# Bodenplatine_v001.net
KiCad netlist of a schematic drawn in EAGLE
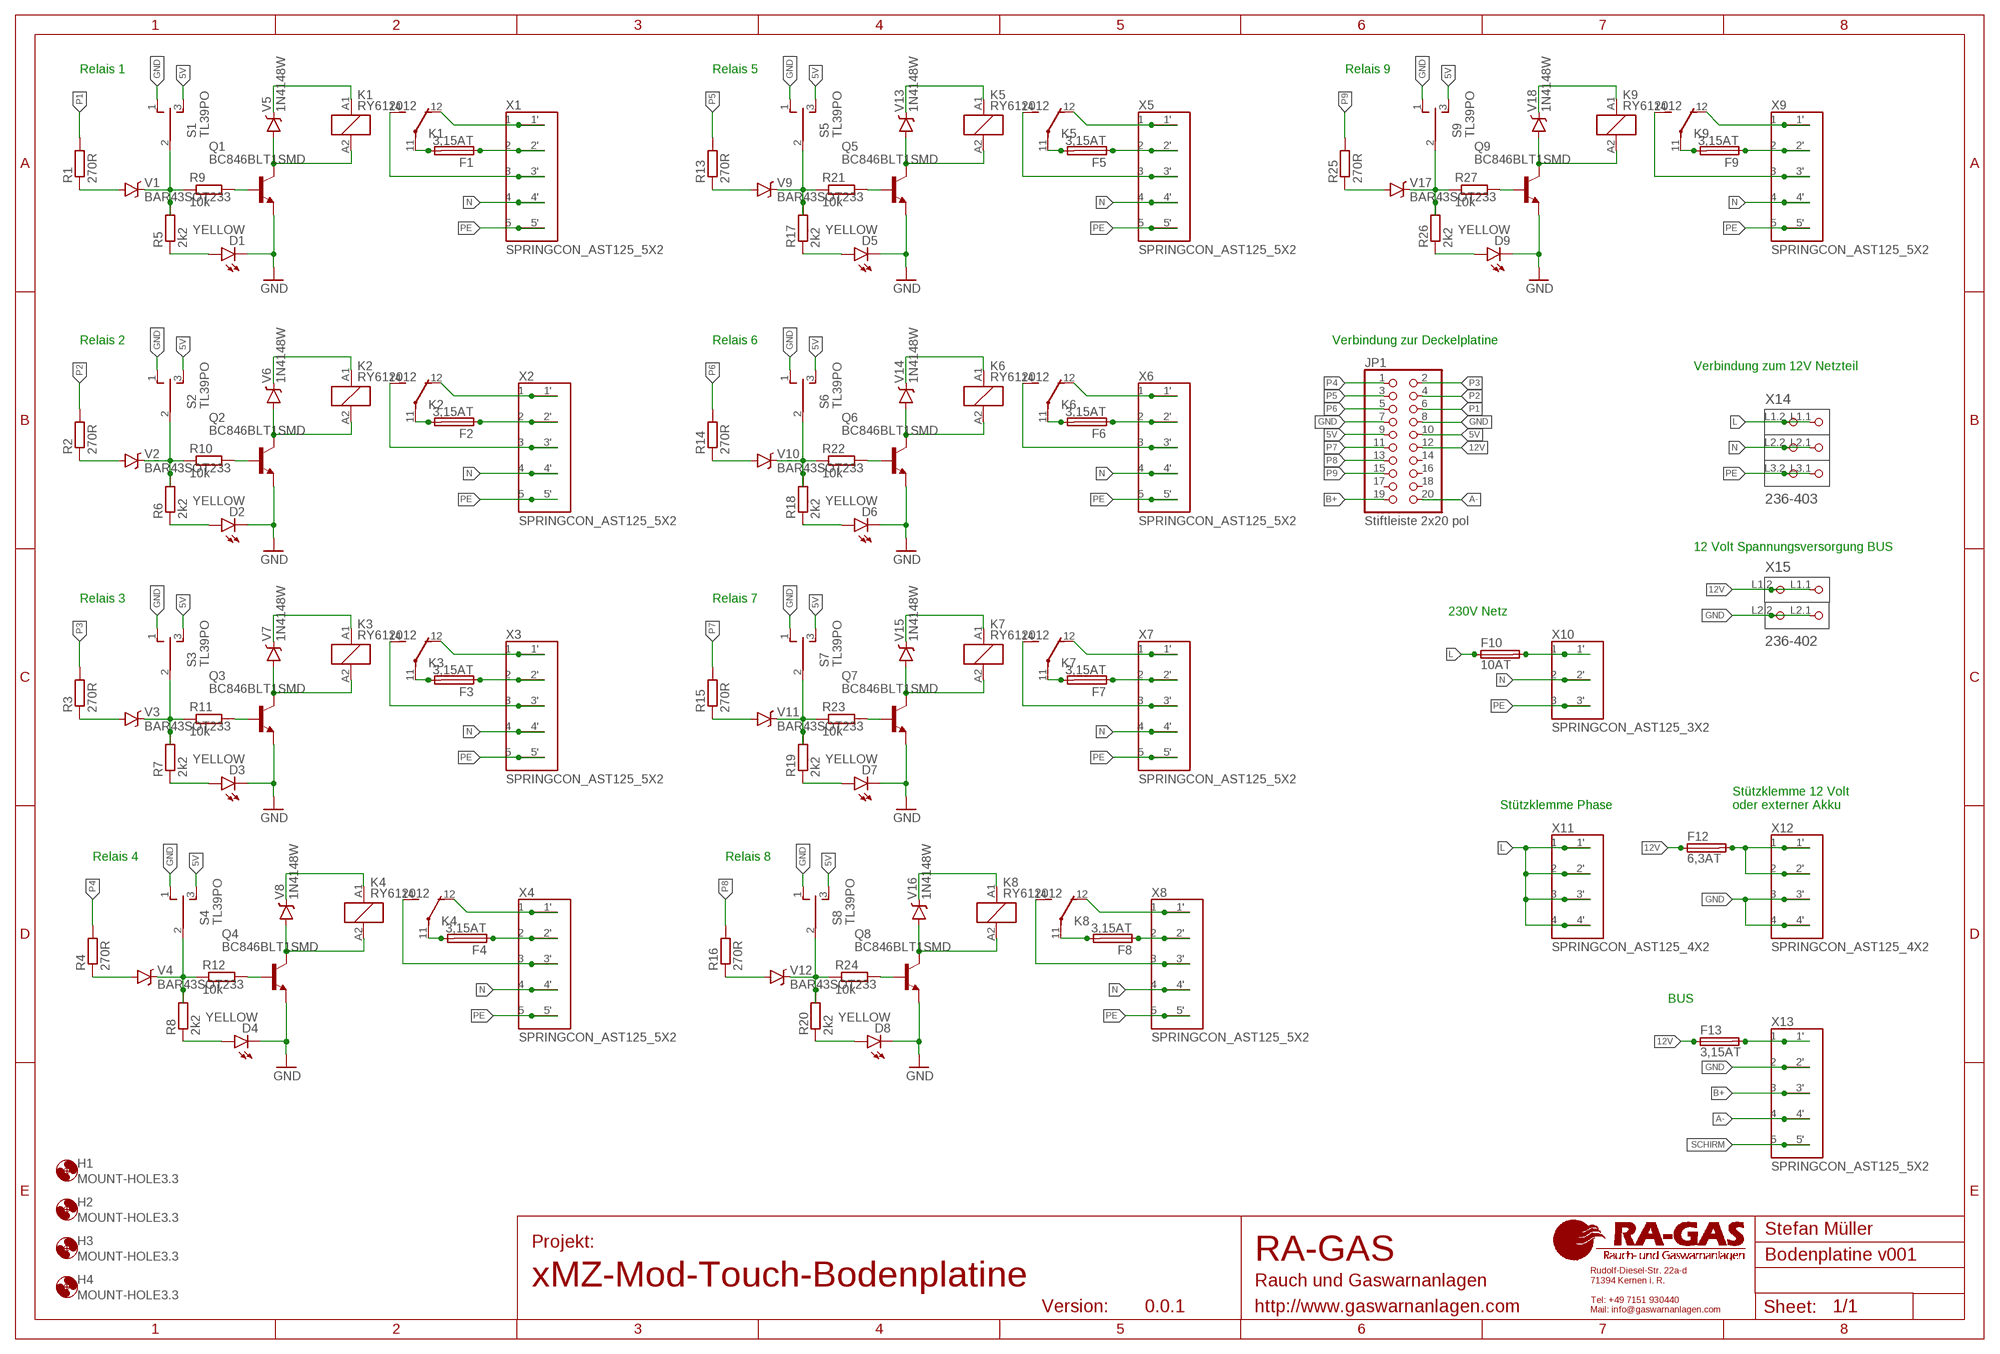
[diagram p0: schematic, sheet 1]

(export (version "E")
  (design (tool "Eeschema 10.0.6"))
  (components
    (comp (ref "D1")
      (value "YELLOW")
      (footprint "eagle-import:LED-1206")
      (fields (field (name "MF") "KINGBRIGHT") (field (name "MPN") "KP-3216SYC"))
      (libsource (lib "eagle-import") (part "LED-YELLOWLARGE"))
    )
    (comp (ref "D2")
      (value "YELLOW")
      (footprint "eagle-import:LED-1206")
      (fields (field (name "MF") "KINGBRIGHT") (field (name "MPN") "KP-3216SYC"))
      (libsource (lib "eagle-import") (part "LED-YELLOWLARGE"))
    )
    (comp (ref "D3")
      (value "YELLOW")
      (footprint "eagle-import:LED-1206")
      (fields (field (name "MF") "KINGBRIGHT") (field (name "MPN") "KP-3216SYC"))
      (libsource (lib "eagle-import") (part "LED-YELLOWLARGE"))
    )
    (comp (ref "D4")
      (value "YELLOW")
      (footprint "eagle-import:LED-1206")
      (fields (field (name "MF") "KINGBRIGHT") (field (name "MPN") "KP-3216SYC"))
      (libsource (lib "eagle-import") (part "LED-YELLOWLARGE"))
    )
    (comp (ref "D5")
      (value "YELLOW")
      (footprint "eagle-import:LED-1206")
      (fields (field (name "MF") "KINGBRIGHT") (field (name "MPN") "KP-3216SYC"))
      (libsource (lib "eagle-import") (part "LED-YELLOWLARGE"))
    )
    (comp (ref "D6")
      (value "YELLOW")
      (footprint "eagle-import:LED-1206")
      (fields (field (name "MF") "KINGBRIGHT") (field (name "MPN") "KP-3216SYC"))
      (libsource (lib "eagle-import") (part "LED-YELLOWLARGE"))
    )
    (comp (ref "D7")
      (value "YELLOW")
      (footprint "eagle-import:LED-1206")
      (fields (field (name "MF") "KINGBRIGHT") (field (name "MPN") "KP-3216SYC"))
      (libsource (lib "eagle-import") (part "LED-YELLOWLARGE"))
    )
    (comp (ref "D8")
      (value "YELLOW")
      (footprint "eagle-import:LED-1206")
      (fields (field (name "MF") "KINGBRIGHT") (field (name "MPN") "KP-3216SYC"))
      (libsource (lib "eagle-import") (part "LED-YELLOWLARGE"))
    )
    (comp (ref "D9")
      (value "YELLOW")
      (footprint "eagle-import:LED-1206")
      (fields (field (name "MF") "KINGBRIGHT") (field (name "MPN") "KP-3216SYC"))
      (libsource (lib "eagle-import") (part "LED-YELLOWLARGE"))
    )
    (comp (ref "F1")
      (value "3,15AT")
      (footprint "eagle-import:FPG4")
      (libsource (lib "eagle-import") (part "FPG4"))
    )
    (comp (ref "F2")
      (value "3,15AT")
      (footprint "eagle-import:FPG4")
      (libsource (lib "eagle-import") (part "FPG4"))
    )
    (comp (ref "F3")
      (value "3,15AT")
      (footprint "eagle-import:FPG4")
      (libsource (lib "eagle-import") (part "FPG4"))
    )
    (comp (ref "F4")
      (value "3,15AT")
      (footprint "eagle-import:FPG4")
      (libsource (lib "eagle-import") (part "FPG4"))
    )
    (comp (ref "F5")
      (value "3,15AT")
      (footprint "eagle-import:FPG4")
      (libsource (lib "eagle-import") (part "FPG4"))
    )
    (comp (ref "F6")
      (value "3,15AT")
      (footprint "eagle-import:FPG4")
      (libsource (lib "eagle-import") (part "FPG4"))
    )
    (comp (ref "F7")
      (value "3,15AT")
      (footprint "eagle-import:FPG4")
      (libsource (lib "eagle-import") (part "FPG4"))
    )
    (comp (ref "F8")
      (value "3,15AT")
      (footprint "eagle-import:FPG4")
      (libsource (lib "eagle-import") (part "FPG4"))
    )
    (comp (ref "F9")
      (value "3,15AT")
      (footprint "eagle-import:FPG4")
      (libsource (lib "eagle-import") (part "FPG4"))
    )
    (comp (ref "F10")
      (value "10AT")
      (footprint "eagle-import:FPG4")
      (libsource (lib "eagle-import") (part "FPG4"))
    )
    (comp (ref "F12")
      (value "6,3AT")
      (footprint "eagle-import:FPG4")
      (libsource (lib "eagle-import") (part "FPG4"))
    )
    (comp (ref "F13")
      (value "3,15AT")
      (footprint "eagle-import:FPG4")
      (libsource (lib "eagle-import") (part "FPG4"))
    )
    (comp (ref "H1")
      (value "MOUNT-HOLE3.3")
      (footprint "eagle-import:3,3")
      (libsource (lib "eagle-import") (part "MOUNT-HOLE3.3"))
    )
    (comp (ref "H2")
      (value "MOUNT-HOLE3.3")
      (footprint "eagle-import:3,3")
      (libsource (lib "eagle-import") (part "MOUNT-HOLE3.3"))
    )
    (comp (ref "H3")
      (value "MOUNT-HOLE3.3")
      (footprint "eagle-import:3,3")
      (libsource (lib "eagle-import") (part "MOUNT-HOLE3.3"))
    )
    (comp (ref "H4")
      (value "MOUNT-HOLE3.3")
      (footprint "eagle-import:3,3")
      (libsource (lib "eagle-import") (part "MOUNT-HOLE3.3"))
    )
    (comp (ref "JP1")
      (value "Stiftleiste 2x20 pol")
      (footprint "eagle-import:2X10")
      (fields (field (name "MF") "TE CONNECTIVITY / AMP") (field (name "MPN") "825440-5"))
      (libsource (lib "eagle-import") (part "PINHD-2X10"))
    )
    (comp (ref "K1")
      (value "RY612012")
      (footprint "eagle-import:RY-II")
      (fields
        (field (name "MF") "TYCO ELECTRONICS")
        (field (name "MF_1") "TE CONNECTIVITY / SCHRACK")
        (field (name "MPN") "V23061B1005A301")
        (field (name "OC_FARNELL") "1023958")
      )
      (libsource (lib "eagle-import") (part "RY?162012"))
    )
    (comp (ref "K2")
      (value "RY612012")
      (footprint "eagle-import:RY-II")
      (fields
        (field (name "MF") "TYCO ELECTRONICS")
        (field (name "MF_1") "TE CONNECTIVITY / SCHRACK")
        (field (name "MPN") "V23061B1005A301")
        (field (name "OC_FARNELL") "1023958")
      )
      (libsource (lib "eagle-import") (part "RY?162012"))
    )
    (comp (ref "K3")
      (value "RY612012")
      (footprint "eagle-import:RY-II")
      (fields
        (field (name "MF") "TYCO ELECTRONICS")
        (field (name "MF_1") "TE CONNECTIVITY / SCHRACK")
        (field (name "MPN") "V23061B1005A301")
        (field (name "OC_FARNELL") "1023958")
      )
      (libsource (lib "eagle-import") (part "RY?162012"))
    )
    (comp (ref "K4")
      (value "RY612012")
      (footprint "eagle-import:RY-II")
      (fields
        (field (name "MF") "TYCO ELECTRONICS")
        (field (name "MF_1") "TE CONNECTIVITY / SCHRACK")
        (field (name "MPN") "V23061B1005A301")
        (field (name "OC_FARNELL") "1023958")
      )
      (libsource (lib "eagle-import") (part "RY?162012"))
    )
    (comp (ref "K5")
      (value "RY612012")
      (footprint "eagle-import:RY-II")
      (fields
        (field (name "MF") "TYCO ELECTRONICS")
        (field (name "MF_1") "TE CONNECTIVITY / SCHRACK")
        (field (name "MPN") "V23061B1005A301")
        (field (name "OC_FARNELL") "1023958")
      )
      (libsource (lib "eagle-import") (part "RY?162012"))
    )
    (comp (ref "K6")
      (value "RY612012")
      (footprint "eagle-import:RY-II")
      (fields
        (field (name "MF") "TYCO ELECTRONICS")
        (field (name "MF_1") "TE CONNECTIVITY / SCHRACK")
        (field (name "MPN") "V23061B1005A301")
        (field (name "OC_FARNELL") "1023958")
      )
      (libsource (lib "eagle-import") (part "RY?162012"))
    )
    (comp (ref "K7")
      (value "RY612012")
      (footprint "eagle-import:RY-II")
      (fields
        (field (name "MF") "TYCO ELECTRONICS")
        (field (name "MF_1") "TE CONNECTIVITY / SCHRACK")
        (field (name "MPN") "V23061B1005A301")
        (field (name "OC_FARNELL") "1023958")
      )
      (libsource (lib "eagle-import") (part "RY?162012"))
    )
    (comp (ref "K8")
      (value "RY612012")
      (footprint "eagle-import:RY-II")
      (fields
        (field (name "MF") "TYCO ELECTRONICS")
        (field (name "MF_1") "TE CONNECTIVITY / SCHRACK")
        (field (name "MPN") "V23061B1005A301")
        (field (name "OC_FARNELL") "1023958")
      )
      (libsource (lib "eagle-import") (part "RY?162012"))
    )
    (comp (ref "K9")
      (value "RY612012")
      (footprint "eagle-import:RY-II")
      (fields
        (field (name "MF") "TYCO ELECTRONICS")
        (field (name "MF_1") "TE CONNECTIVITY / SCHRACK")
        (field (name "MPN") "V23061B1005A301")
        (field (name "OC_FARNELL") "1023958")
      )
      (libsource (lib "eagle-import") (part "RY?162012"))
    )
    (comp (ref "Q1")
      (value "BC846BLT1SMD")
      (footprint "eagle-import:SOT23")
      (fields (field (name "MF") "ON SEMICONDUCTOR") (field (name "MPN") "BC846BWT1G"))
      (libsource (lib "eagle-import") (part "BC846SMDBLT1"))
    )
    (comp (ref "Q2")
      (value "BC846BLT1SMD")
      (footprint "eagle-import:SOT23")
      (fields (field (name "MF") "ON SEMICONDUCTOR") (field (name "MPN") "BC846BWT1G"))
      (libsource (lib "eagle-import") (part "BC846SMDBLT1"))
    )
    (comp (ref "Q3")
      (value "BC846BLT1SMD")
      (footprint "eagle-import:SOT23")
      (fields (field (name "MF") "ON SEMICONDUCTOR") (field (name "MPN") "BC846BWT1G"))
      (libsource (lib "eagle-import") (part "BC846SMDBLT1"))
    )
    (comp (ref "Q4")
      (value "BC846BLT1SMD")
      (footprint "eagle-import:SOT23")
      (fields (field (name "MF") "ON SEMICONDUCTOR") (field (name "MPN") "BC846BWT1G"))
      (libsource (lib "eagle-import") (part "BC846SMDBLT1"))
    )
    (comp (ref "Q5")
      (value "BC846BLT1SMD")
      (footprint "eagle-import:SOT23")
      (fields (field (name "MF") "ON SEMICONDUCTOR") (field (name "MPN") "BC846BWT1G"))
      (libsource (lib "eagle-import") (part "BC846SMDBLT1"))
    )
    (comp (ref "Q6")
      (value "BC846BLT1SMD")
      (footprint "eagle-import:SOT23")
      (fields (field (name "MF") "ON SEMICONDUCTOR") (field (name "MPN") "BC846BWT1G"))
      (libsource (lib "eagle-import") (part "BC846SMDBLT1"))
    )
    (comp (ref "Q7")
      (value "BC846BLT1SMD")
      (footprint "eagle-import:SOT23")
      (fields (field (name "MF") "ON SEMICONDUCTOR") (field (name "MPN") "BC846BWT1G"))
      (libsource (lib "eagle-import") (part "BC846SMDBLT1"))
    )
    (comp (ref "Q8")
      (value "BC846BLT1SMD")
      (footprint "eagle-import:SOT23")
      (fields (field (name "MF") "ON SEMICONDUCTOR") (field (name "MPN") "BC846BWT1G"))
      (libsource (lib "eagle-import") (part "BC846SMDBLT1"))
    )
    (comp (ref "Q9")
      (value "BC846BLT1SMD")
      (footprint "eagle-import:SOT23")
      (fields (field (name "MF") "ON SEMICONDUCTOR") (field (name "MPN") "BC846BWT1G"))
      (libsource (lib "eagle-import") (part "BC846SMDBLT1"))
    )
    (comp (ref "R1")
      (value "270R")
      (footprint "eagle-import:M0805")
      (fields (field (name "MF") "MULTICOMP") (field (name "MPN") "MC01W08055270R"))
      (libsource (lib "eagle-import") (part "R-EU_M0805"))
    )
    (comp (ref "R2")
      (value "270R")
      (footprint "eagle-import:M0805")
      (fields (field (name "MF") "MULTICOMP") (field (name "MPN") "MC01W08055270R"))
      (libsource (lib "eagle-import") (part "R-EU_M0805"))
    )
    (comp (ref "R3")
      (value "270R")
      (footprint "eagle-import:M0805")
      (fields (field (name "MF") "MULTICOMP") (field (name "MPN") "MC01W08055270R"))
      (libsource (lib "eagle-import") (part "R-EU_M0805"))
    )
    (comp (ref "R4")
      (value "270R")
      (footprint "eagle-import:M0805")
      (fields (field (name "MF") "MULTICOMP") (field (name "MPN") "MC01W08055270R"))
      (libsource (lib "eagle-import") (part "R-EU_M0805"))
    )
    (comp (ref "R5")
      (value "2k2")
      (footprint "eagle-import:R0603")
      (fields (field (name "MF") "MULTICOMP") (field (name "MPN") "MC0063W060352K2"))
      (libsource (lib "eagle-import") (part "R-EU_R0603"))
    )
    (comp (ref "R6")
      (value "2k2")
      (footprint "eagle-import:R0603")
      (fields (field (name "MF") "MULTICOMP") (field (name "MPN") "MC0063W060352K2"))
      (libsource (lib "eagle-import") (part "R-EU_R0603"))
    )
    (comp (ref "R7")
      (value "2k2")
      (footprint "eagle-import:R0603")
      (fields (field (name "MF") "MULTICOMP") (field (name "MPN") "MC0063W060352K2"))
      (libsource (lib "eagle-import") (part "R-EU_R0603"))
    )
    (comp (ref "R8")
      (value "2k2")
      (footprint "eagle-import:R0603")
      (fields (field (name "MF") "MULTICOMP") (field (name "MPN") "MC0063W060352K2"))
      (libsource (lib "eagle-import") (part "R-EU_R0603"))
    )
    (comp (ref "R9")
      (value "10k")
      (footprint "eagle-import:R0603")
      (fields (field (name "MF") "TE CONNECTIVITY / NEOHM") (field (name "MPN") "CPF0603B10KE1"))
      (libsource (lib "eagle-import") (part "R-EU_R0603"))
    )
    (comp (ref "R10")
      (value "10k")
      (footprint "eagle-import:R0603")
      (fields (field (name "MF") "TE CONNECTIVITY / NEOHM") (field (name "MPN") "CPF0603B10KE1"))
      (libsource (lib "eagle-import") (part "R-EU_R0603"))
    )
    (comp (ref "R11")
      (value "10k")
      (footprint "eagle-import:R0603")
      (fields (field (name "MF") "TE CONNECTIVITY / NEOHM") (field (name "MPN") "CPF0603B10KE1"))
      (libsource (lib "eagle-import") (part "R-EU_R0603"))
    )
    (comp (ref "R12")
      (value "10k")
      (footprint "eagle-import:R0603")
      (fields (field (name "MF") "TE CONNECTIVITY / NEOHM") (field (name "MPN") "CPF0603B10KE1"))
      (libsource (lib "eagle-import") (part "R-EU_R0603"))
    )
    (comp (ref "R13")
      (value "270R")
      (footprint "eagle-import:M0805")
      (fields (field (name "MF") "MULTICOMP") (field (name "MPN") "MC01W08055270R"))
      (libsource (lib "eagle-import") (part "R-EU_M0805"))
    )
    (comp (ref "R14")
      (value "270R")
      (footprint "eagle-import:M0805")
      (fields (field (name "MF") "MULTICOMP") (field (name "MPN") "MC01W08055270R"))
      (libsource (lib "eagle-import") (part "R-EU_M0805"))
    )
    (comp (ref "R15")
      (value "270R")
      (footprint "eagle-import:M0805")
      (fields (field (name "MF") "MULTICOMP") (field (name "MPN") "MC01W08055270R"))
      (libsource (lib "eagle-import") (part "R-EU_M0805"))
    )
    (comp (ref "R16")
      (value "270R")
      (footprint "eagle-import:M0805")
      (fields (field (name "MF") "MULTICOMP") (field (name "MPN") "MC01W08055270R"))
      (libsource (lib "eagle-import") (part "R-EU_M0805"))
    )
    (comp (ref "R17")
      (value "2k2")
      (footprint "eagle-import:R0603")
      (fields (field (name "MF") "MULTICOMP") (field (name "MPN") "MC0063W060352K2"))
      (libsource (lib "eagle-import") (part "R-EU_R0603"))
    )
    (comp (ref "R18")
      (value "2k2")
      (footprint "eagle-import:R0603")
      (fields (field (name "MF") "MULTICOMP") (field (name "MPN") "MC0063W060352K2"))
      (libsource (lib "eagle-import") (part "R-EU_R0603"))
    )
    (comp (ref "R19")
      (value "2k2")
      (footprint "eagle-import:R0603")
      (fields (field (name "MF") "MULTICOMP") (field (name "MPN") "MC0063W060352K2"))
      (libsource (lib "eagle-import") (part "R-EU_R0603"))
    )
    (comp (ref "R20")
      (value "2k2")
      (footprint "eagle-import:R0603")
      (fields (field (name "MF") "MULTICOMP") (field (name "MPN") "MC0063W060352K2"))
      (libsource (lib "eagle-import") (part "R-EU_R0603"))
    )
    (comp (ref "R21")
      (value "10k")
      (footprint "eagle-import:R0603")
      (fields (field (name "MF") "TE CONNECTIVITY / NEOHM") (field (name "MPN") "CPF0603B10KE1"))
      (libsource (lib "eagle-import") (part "R-EU_R0603"))
    )
    (comp (ref "R22")
      (value "10k")
      (footprint "eagle-import:R0603")
      (fields (field (name "MF") "TE CONNECTIVITY / NEOHM") (field (name "MPN") "CPF0603B10KE1"))
      (libsource (lib "eagle-import") (part "R-EU_R0603"))
    )
    (comp (ref "R23")
      (value "10k")
      (footprint "eagle-import:R0603")
      (fields (field (name "MF") "TE CONNECTIVITY / NEOHM") (field (name "MPN") "CPF0603B10KE1"))
      (libsource (lib "eagle-import") (part "R-EU_R0603"))
    )
    (comp (ref "R24")
      (value "10k")
      (footprint "eagle-import:R0603")
      (fields (field (name "MF") "TE CONNECTIVITY / NEOHM") (field (name "MPN") "CPF0603B10KE1"))
      (libsource (lib "eagle-import") (part "R-EU_R0603"))
    )
    (comp (ref "R25")
      (value "270R")
      (footprint "eagle-import:M0805")
      (fields (field (name "MF") "MULTICOMP") (field (name "MPN") "MC01W08055270R"))
      (libsource (lib "eagle-import") (part "R-EU_M0805"))
    )
    (comp (ref "R26")
      (value "2k2")
      (footprint "eagle-import:R0603")
      (fields (field (name "MF") "MULTICOMP") (field (name "MPN") "MC0063W060352K2"))
      (libsource (lib "eagle-import") (part "R-EU_R0603"))
    )
    (comp (ref "R27")
      (value "10k")
      (footprint "eagle-import:R0603")
      (fields (field (name "MF") "TE CONNECTIVITY / NEOHM") (field (name "MPN") "CPF0603B10KE1"))
      (libsource (lib "eagle-import") (part "R-EU_R0603"))
    )
    (comp (ref "S1")
      (value "TL39PO")
      (footprint "eagle-import:TL3XPO")
      (fields (field (name "MF") "TE CONNECTIVITY / ALCOSWITCH") (field (name "MPN") "A103SYCQ04"))
      (libsource (lib "eagle-import") (part "TL39PO"))
    )
    (comp (ref "S2")
      (value "TL39PO")
      (footprint "eagle-import:TL3XPO")
      (fields (field (name "MF") "TE CONNECTIVITY / ALCOSWITCH") (field (name "MPN") "A103SYCQ04"))
      (libsource (lib "eagle-import") (part "TL39PO"))
    )
    (comp (ref "S3")
      (value "TL39PO")
      (footprint "eagle-import:TL3XPO")
      (fields (field (name "MF") "TE CONNECTIVITY / ALCOSWITCH") (field (name "MPN") "A103SYCQ04"))
      (libsource (lib "eagle-import") (part "TL39PO"))
    )
    (comp (ref "S4")
      (value "TL39PO")
      (footprint "eagle-import:TL3XPO")
      (fields (field (name "MF") "TE CONNECTIVITY / ALCOSWITCH") (field (name "MPN") "A103SYCQ04"))
      (libsource (lib "eagle-import") (part "TL39PO"))
    )
    (comp (ref "S5")
      (value "TL39PO")
      (footprint "eagle-import:TL3XPO")
      (fields (field (name "MF") "TE CONNECTIVITY / ALCOSWITCH") (field (name "MPN") "A103SYCQ04"))
      (libsource (lib "eagle-import") (part "TL39PO"))
    )
    (comp (ref "S6")
      (value "TL39PO")
      (footprint "eagle-import:TL3XPO")
      (fields (field (name "MF") "TE CONNECTIVITY / ALCOSWITCH") (field (name "MPN") "A103SYCQ04"))
      (libsource (lib "eagle-import") (part "TL39PO"))
    )
    (comp (ref "S7")
      (value "TL39PO")
      (footprint "eagle-import:TL3XPO")
      (fields (field (name "MF") "TE CONNECTIVITY / ALCOSWITCH") (field (name "MPN") "A103SYCQ04"))
      (libsource (lib "eagle-import") (part "TL39PO"))
    )
    (comp (ref "S8")
      (value "TL39PO")
      (footprint "eagle-import:TL3XPO")
      (fields (field (name "MF") "TE CONNECTIVITY / ALCOSWITCH") (field (name "MPN") "A103SYCQ04"))
      (libsource (lib "eagle-import") (part "TL39PO"))
    )
    (comp (ref "S9")
      (value "TL39PO")
      (footprint "eagle-import:TL3XPO")
      (fields (field (name "MF") "TE CONNECTIVITY / ALCOSWITCH") (field (name "MPN") "A103SYCQ04"))
      (libsource (lib "eagle-import") (part "TL39PO"))
    )
    (comp (ref "V1")
      (value "BAR43SOT233")
      (footprint "eagle-import:SOT23")
      (fields (field (name "MF") "FAIRCHILD SEMICONDUCTOR") (field (name "MPN") "BAR43"))
      (libsource (lib "eagle-import") (part "BAR43SOT233"))
    )
    (comp (ref "V2")
      (value "BAR43SOT233")
      (footprint "eagle-import:SOT23")
      (fields (field (name "MF") "FAIRCHILD SEMICONDUCTOR") (field (name "MPN") "BAR43"))
      (libsource (lib "eagle-import") (part "BAR43SOT233"))
    )
    (comp (ref "V3")
      (value "BAR43SOT233")
      (footprint "eagle-import:SOT23")
      (fields (field (name "MF") "FAIRCHILD SEMICONDUCTOR") (field (name "MPN") "BAR43"))
      (libsource (lib "eagle-import") (part "BAR43SOT233"))
    )
    (comp (ref "V4")
      (value "BAR43SOT233")
      (footprint "eagle-import:SOT23")
      (fields (field (name "MF") "FAIRCHILD SEMICONDUCTOR") (field (name "MPN") "BAR43"))
      (libsource (lib "eagle-import") (part "BAR43SOT233"))
    )
    (comp (ref "V5")
      (value "1N4148W")
      (footprint "eagle-import:MINIMELF")
      (fields (field (name "MF") "VISHAY") (field (name "MPN") "LL4148-GS08"))
      (libsource (lib "eagle-import") (part "LL4148"))
    )
    (comp (ref "V6")
      (value "1N4148W")
      (footprint "eagle-import:MINIMELF")
      (fields (field (name "MF") "VISHAY") (field (name "MPN") "LL4148-GS08"))
      (libsource (lib "eagle-import") (part "LL4148"))
    )
    (comp (ref "V7")
      (value "1N4148W")
      (footprint "eagle-import:MINIMELF")
      (fields (field (name "MF") "VISHAY") (field (name "MPN") "LL4148-GS08"))
      (libsource (lib "eagle-import") (part "LL4148"))
    )
    (comp (ref "V8")
      (value "1N4148W")
      (footprint "eagle-import:MINIMELF")
      (fields (field (name "MF") "VISHAY") (field (name "MPN") "LL4148-GS08"))
      (libsource (lib "eagle-import") (part "LL4148"))
    )
    (comp (ref "V9")
      (value "BAR43SOT233")
      (footprint "eagle-import:SOT23")
      (fields (field (name "MF") "FAIRCHILD SEMICONDUCTOR") (field (name "MPN") "BAR43"))
      (libsource (lib "eagle-import") (part "BAR43SOT233"))
    )
    (comp (ref "V10")
      (value "BAR43SOT233")
      (footprint "eagle-import:SOT23")
      (fields (field (name "MF") "FAIRCHILD SEMICONDUCTOR") (field (name "MPN") "BAR43"))
      (libsource (lib "eagle-import") (part "BAR43SOT233"))
    )
    (comp (ref "V11")
      (value "BAR43SOT233")
      (footprint "eagle-import:SOT23")
      (fields (field (name "MF") "FAIRCHILD SEMICONDUCTOR") (field (name "MPN") "BAR43"))
      (libsource (lib "eagle-import") (part "BAR43SOT233"))
    )
    (comp (ref "V12")
      (value "BAR43SOT233")
      (footprint "eagle-import:SOT23")
      (fields (field (name "MF") "FAIRCHILD SEMICONDUCTOR") (field (name "MPN") "BAR43"))
      (libsource (lib "eagle-import") (part "BAR43SOT233"))
    )
    (comp (ref "V13")
      (value "1N4148W")
      (footprint "eagle-import:MINIMELF")
      (fields (field (name "MF") "VISHAY") (field (name "MPN") "LL4148-GS08"))
      (libsource (lib "eagle-import") (part "LL4148"))
    )
    (comp (ref "V14")
      (value "1N4148W")
      (footprint "eagle-import:MINIMELF")
      (fields (field (name "MF") "VISHAY") (field (name "MPN") "LL4148-GS08"))
      (libsource (lib "eagle-import") (part "LL4148"))
    )
    (comp (ref "V15")
      (value "1N4148W")
      (footprint "eagle-import:MINIMELF")
      (fields (field (name "MF") "VISHAY") (field (name "MPN") "LL4148-GS08"))
      (libsource (lib "eagle-import") (part "LL4148"))
    )
    (comp (ref "V16")
      (value "1N4148W")
      (footprint "eagle-import:MINIMELF")
      (fields (field (name "MF") "VISHAY") (field (name "MPN") "LL4148-GS08"))
      (libsource (lib "eagle-import") (part "LL4148"))
    )
    (comp (ref "V17")
      (value "BAR43SOT233")
      (footprint "eagle-import:SOT23")
      (fields (field (name "MF") "FAIRCHILD SEMICONDUCTOR") (field (name "MPN") "BAR43"))
      (libsource (lib "eagle-import") (part "BAR43SOT233"))
    )
    (comp (ref "V18")
      (value "1N4148W")
      (footprint "eagle-import:MINIMELF")
      (fields (field (name "MF") "VISHAY") (field (name "MPN") "LL4148-GS08"))
      (libsource (lib "eagle-import") (part "LL4148"))
    )
    (comp (ref "X1")
      (value "SPRINGCON_AST125_5X2")
      (footprint "eagle-import:SPRINGCON_AST125_5X2")
      (libsource (lib "eagle-import") (part "SPRINGCON_AST125_5X2"))
    )
    (comp (ref "X2")
      (value "SPRINGCON_AST125_5X2")
      (footprint "eagle-import:SPRINGCON_AST125_5X2")
      (libsource (lib "eagle-import") (part "SPRINGCON_AST125_5X2"))
    )
    (comp (ref "X3")
      (value "SPRINGCON_AST125_5X2")
      (footprint "eagle-import:SPRINGCON_AST125_5X2")
      (libsource (lib "eagle-import") (part "SPRINGCON_AST125_5X2"))
    )
    (comp (ref "X4")
      (value "SPRINGCON_AST125_5X2")
      (footprint "eagle-import:SPRINGCON_AST125_5X2")
      (libsource (lib "eagle-import") (part "SPRINGCON_AST125_5X2"))
    )
    (comp (ref "X5")
      (value "SPRINGCON_AST125_5X2")
      (footprint "eagle-import:SPRINGCON_AST125_5X2")
      (libsource (lib "eagle-import") (part "SPRINGCON_AST125_5X2"))
    )
    (comp (ref "X6")
      (value "SPRINGCON_AST125_5X2")
      (footprint "eagle-import:SPRINGCON_AST125_5X2")
      (libsource (lib "eagle-import") (part "SPRINGCON_AST125_5X2"))
    )
    (comp (ref "X7")
      (value "SPRINGCON_AST125_5X2")
      (footprint "eagle-import:SPRINGCON_AST125_5X2")
      (libsource (lib "eagle-import") (part "SPRINGCON_AST125_5X2"))
    )
    (comp (ref "X8")
      (value "SPRINGCON_AST125_5X2")
      (footprint "eagle-import:SPRINGCON_AST125_5X2")
      (libsource (lib "eagle-import") (part "SPRINGCON_AST125_5X2"))
    )
    (comp (ref "X9")
      (value "SPRINGCON_AST125_5X2")
      (footprint "eagle-import:SPRINGCON_AST125_5X2")
      (libsource (lib "eagle-import") (part "SPRINGCON_AST125_5X2"))
    )
    (comp (ref "X10")
      (value "SPRINGCON_AST125_3X2")
      (footprint "eagle-import:SPRINGCON_AST125_3X2")
      (libsource (lib "eagle-import") (part "SPRINGCON_AST125_3X2"))
    )
    (comp (ref "X11")
      (value "SPRINGCON_AST125_4X2")
      (footprint "eagle-import:SPRINGCON_AST125_4X2")
      (libsource (lib "eagle-import") (part "SPRINGCON_AST125_4X2"))
    )
    (comp (ref "X12")
      (value "SPRINGCON_AST125_4X2")
      (footprint "eagle-import:SPRINGCON_AST125_4X2")
      (libsource (lib "eagle-import") (part "SPRINGCON_AST125_4X2"))
    )
    (comp (ref "X13")
      (value "SPRINGCON_AST125_5X2")
      (footprint "eagle-import:SPRINGCON_AST125_5X2")
      (libsource (lib "eagle-import") (part "SPRINGCON_AST125_5X2"))
    )
    (comp (ref "X14")
      (value "236-403")
      (footprint "eagle-import:P-236-403")
      (fields (field (name "MF") "WAGO"))
      (libsource (lib "eagle-import") (part "236-403"))
    )
    (comp (ref "X15")
      (value "236-402")
      (footprint "eagle-import:P-236-402")
      (fields (field (name "MF") "WAGO"))
      (libsource (lib "eagle-import") (part "236-402"))
    )
  )
  (nets
    (net (code "1") (name "5V") (class "Default")
      (node (ref "JP1") (pin "10") (pinfunction "10_10") (pintype "passive"))
      (node (ref "JP1") (pin "9") (pinfunction "9_9") (pintype "passive"))
      (node (ref "S1") (pin "3") (pinfunction "S_3") (pintype "passive"))
      (node (ref "S2") (pin "3") (pinfunction "S_3") (pintype "passive"))
      (node (ref "S3") (pin "3") (pinfunction "S_3") (pintype "passive"))
      (node (ref "S4") (pin "3") (pinfunction "S_3") (pintype "passive"))
      (node (ref "S5") (pin "3") (pinfunction "S_3") (pintype "passive"))
      (node (ref "S6") (pin "3") (pinfunction "S_3") (pintype "passive"))
      (node (ref "S7") (pin "3") (pinfunction "S_3") (pintype "passive"))
      (node (ref "S8") (pin "3") (pinfunction "S_3") (pintype "passive"))
      (node (ref "S9") (pin "3") (pinfunction "S_3") (pintype "passive"))
    )
    (net (code "2") (name "12V") (class "Default")
      (node (ref "F12") (pin "1") (pinfunction "1_1") (pintype "passive"))
      (node (ref "F12") (pin "1'") (pinfunction "1_1'") (pintype "passive"))
      (node (ref "F13") (pin "1") (pinfunction "1_1") (pintype "passive"))
      (node (ref "F13") (pin "1'") (pinfunction "1_1'") (pintype "passive"))
      (node (ref "JP1") (pin "12") (pinfunction "12_12") (pintype "passive"))
      (node (ref "X15") (pin "L1.1") (pinfunction "P1.1_L1.1") (pintype "bidirectional"))
      (node (ref "X15") (pin "L1.2") (pinfunction "P1.2_L1.2") (pintype "bidirectional"))
    )
    (net (code "3") (name "A-") (class "Default")
      (node (ref "JP1") (pin "20") (pinfunction "20_20") (pintype "passive"))
      (node (ref "X13") (pin "4") (pinfunction "4_4") (pintype "passive"))
      (node (ref "X13") (pin "4'") (pinfunction "4_4'") (pintype "passive"))
    )
    (net (code "4") (name "B+") (class "Default")
      (node (ref "JP1") (pin "19") (pinfunction "19_19") (pintype "passive"))
      (node (ref "X13") (pin "3") (pinfunction "3_3") (pintype "passive"))
      (node (ref "X13") (pin "3'") (pinfunction "3_3'") (pintype "passive"))
    )
    (net (code "5") (name "GND") (class "Default")
      (node (ref "D1") (pin "C") (pinfunction "C_C") (pintype "passive"))
      (node (ref "D2") (pin "C") (pinfunction "C_C") (pintype "passive"))
      (node (ref "D3") (pin "C") (pinfunction "C_C") (pintype "passive"))
      (node (ref "D4") (pin "C") (pinfunction "C_C") (pintype "passive"))
      (node (ref "D5") (pin "C") (pinfunction "C_C") (pintype "passive"))
      (node (ref "D6") (pin "C") (pinfunction "C_C") (pintype "passive"))
      (node (ref "D7") (pin "C") (pinfunction "C_C") (pintype "passive"))
      (node (ref "D8") (pin "C") (pinfunction "C_C") (pintype "passive"))
      (node (ref "D9") (pin "C") (pinfunction "C_C") (pintype "passive"))
      (node (ref "JP1") (pin "7") (pinfunction "7_7") (pintype "passive"))
      (node (ref "JP1") (pin "8") (pinfunction "8_8") (pintype "passive"))
      (node (ref "Q1") (pin "2") (pinfunction "E_2") (pintype "passive"))
      (node (ref "Q2") (pin "2") (pinfunction "E_2") (pintype "passive"))
      (node (ref "Q3") (pin "2") (pinfunction "E_2") (pintype "passive"))
      (node (ref "Q4") (pin "2") (pinfunction "E_2") (pintype "passive"))
      (node (ref "Q5") (pin "2") (pinfunction "E_2") (pintype "passive"))
      (node (ref "Q6") (pin "2") (pinfunction "E_2") (pintype "passive"))
      (node (ref "Q7") (pin "2") (pinfunction "E_2") (pintype "passive"))
      (node (ref "Q8") (pin "2") (pinfunction "E_2") (pintype "passive"))
      (node (ref "Q9") (pin "2") (pinfunction "E_2") (pintype "passive"))
      (node (ref "S1") (pin "1") (pinfunction "O_1") (pintype "passive"))
      (node (ref "S2") (pin "1") (pinfunction "O_1") (pintype "passive"))
      (node (ref "S3") (pin "1") (pinfunction "O_1") (pintype "passive"))
      (node (ref "S4") (pin "1") (pinfunction "O_1") (pintype "passive"))
      (node (ref "S5") (pin "1") (pinfunction "O_1") (pintype "passive"))
      (node (ref "S6") (pin "1") (pinfunction "O_1") (pintype "passive"))
      (node (ref "S7") (pin "1") (pinfunction "O_1") (pintype "passive"))
      (node (ref "S8") (pin "1") (pinfunction "O_1") (pintype "passive"))
      (node (ref "S9") (pin "1") (pinfunction "O_1") (pintype "passive"))
      (node (ref "X12") (pin "3") (pinfunction "3_3") (pintype "passive"))
      (node (ref "X12") (pin "3'") (pinfunction "3_3'") (pintype "passive"))
      (node (ref "X12") (pin "4") (pinfunction "4_4") (pintype "passive"))
      (node (ref "X12") (pin "4'") (pinfunction "4_4'") (pintype "passive"))
      (node (ref "X13") (pin "2") (pinfunction "2_2") (pintype "passive"))
      (node (ref "X13") (pin "2'") (pinfunction "2_2'") (pintype "passive"))
      (node (ref "X15") (pin "L2.1") (pinfunction "P2.1_L2.1") (pintype "bidirectional"))
      (node (ref "X15") (pin "L2.2") (pinfunction "P2.2_L2.2") (pintype "bidirectional"))
    )
    (net (code "6") (name "L") (class "Default")
      (node (ref "F10") (pin "1") (pinfunction "1_1") (pintype "passive"))
      (node (ref "F10") (pin "1'") (pinfunction "1_1'") (pintype "passive"))
      (node (ref "X11") (pin "1") (pinfunction "1_1") (pintype "passive"))
      (node (ref "X11") (pin "1'") (pinfunction "1_1'") (pintype "passive"))
      (node (ref "X11") (pin "2") (pinfunction "2_2") (pintype "passive"))
      (node (ref "X11") (pin "2'") (pinfunction "2_2'") (pintype "passive"))
      (node (ref "X11") (pin "3") (pinfunction "3_3") (pintype "passive"))
      (node (ref "X11") (pin "3'") (pinfunction "3_3'") (pintype "passive"))
      (node (ref "X11") (pin "4") (pinfunction "4_4") (pintype "passive"))
      (node (ref "X11") (pin "4'") (pinfunction "4_4'") (pintype "passive"))
      (node (ref "X14") (pin "L1.1") (pinfunction "P1.1_L1.1") (pintype "bidirectional"))
      (node (ref "X14") (pin "L1.2") (pinfunction "P1.2_L1.2") (pintype "bidirectional"))
    )
    (net (code "7") (name "N") (class "Default")
      (node (ref "X1") (pin "4") (pinfunction "4_4") (pintype "passive"))
      (node (ref "X1") (pin "4'") (pinfunction "4_4'") (pintype "passive"))
      (node (ref "X10") (pin "2") (pinfunction "2_2") (pintype "passive"))
      (node (ref "X10") (pin "2'") (pinfunction "2_2'") (pintype "passive"))
      (node (ref "X14") (pin "L2.1") (pinfunction "P2.1_L2.1") (pintype "bidirectional"))
      (node (ref "X14") (pin "L2.2") (pinfunction "P2.2_L2.2") (pintype "bidirectional"))
      (node (ref "X2") (pin "4") (pinfunction "4_4") (pintype "passive"))
      (node (ref "X2") (pin "4'") (pinfunction "4_4'") (pintype "passive"))
      (node (ref "X3") (pin "4") (pinfunction "4_4") (pintype "passive"))
      (node (ref "X3") (pin "4'") (pinfunction "4_4'") (pintype "passive"))
      (node (ref "X4") (pin "4") (pinfunction "4_4") (pintype "passive"))
      (node (ref "X4") (pin "4'") (pinfunction "4_4'") (pintype "passive"))
      (node (ref "X5") (pin "4") (pinfunction "4_4") (pintype "passive"))
      (node (ref "X5") (pin "4'") (pinfunction "4_4'") (pintype "passive"))
      (node (ref "X6") (pin "4") (pinfunction "4_4") (pintype "passive"))
      (node (ref "X6") (pin "4'") (pinfunction "4_4'") (pintype "passive"))
      (node (ref "X7") (pin "4") (pinfunction "4_4") (pintype "passive"))
      (node (ref "X7") (pin "4'") (pinfunction "4_4'") (pintype "passive"))
      (node (ref "X8") (pin "4") (pinfunction "4_4") (pintype "passive"))
      (node (ref "X8") (pin "4'") (pinfunction "4_4'") (pintype "passive"))
      (node (ref "X9") (pin "4") (pinfunction "4_4") (pintype "passive"))
      (node (ref "X9") (pin "4'") (pinfunction "4_4'") (pintype "passive"))
    )
    (net (code "8") (name "Net-(D1-PadA)") (class "Default")
      (node (ref "D1") (pin "A") (pinfunction "A_A") (pintype "passive"))
      (node (ref "R5") (pin "1") (pinfunction "1_1") (pintype "passive"))
    )
    (net (code "9") (name "Net-(D2-PadA)") (class "Default")
      (node (ref "D2") (pin "A") (pinfunction "A_A") (pintype "passive"))
      (node (ref "R6") (pin "1") (pinfunction "1_1") (pintype "passive"))
    )
    (net (code "10") (name "Net-(D3-PadA)") (class "Default")
      (node (ref "D3") (pin "A") (pinfunction "A_A") (pintype "passive"))
      (node (ref "R7") (pin "1") (pinfunction "1_1") (pintype "passive"))
    )
    (net (code "11") (name "Net-(D4-PadA)") (class "Default")
      (node (ref "D4") (pin "A") (pinfunction "A_A") (pintype "passive"))
      (node (ref "R8") (pin "1") (pinfunction "1_1") (pintype "passive"))
    )
    (net (code "12") (name "Net-(D5-PadA)") (class "Default")
      (node (ref "D5") (pin "A") (pinfunction "A_A") (pintype "passive"))
      (node (ref "R17") (pin "1") (pinfunction "1_1") (pintype "passive"))
    )
    (net (code "13") (name "Net-(D6-PadA)") (class "Default")
      (node (ref "D6") (pin "A") (pinfunction "A_A") (pintype "passive"))
      (node (ref "R18") (pin "1") (pinfunction "1_1") (pintype "passive"))
    )
    (net (code "14") (name "Net-(D7-PadA)") (class "Default")
      (node (ref "D7") (pin "A") (pinfunction "A_A") (pintype "passive"))
      (node (ref "R19") (pin "1") (pinfunction "1_1") (pintype "passive"))
    )
    (net (code "15") (name "Net-(D8-PadA)") (class "Default")
      (node (ref "D8") (pin "A") (pinfunction "A_A") (pintype "passive"))
      (node (ref "R20") (pin "1") (pinfunction "1_1") (pintype "passive"))
    )
    (net (code "16") (name "Net-(D9-PadA)") (class "Default")
      (node (ref "D9") (pin "A") (pinfunction "A_A") (pintype "passive"))
      (node (ref "R26") (pin "1") (pinfunction "1_1") (pintype "passive"))
    )
    (net (code "17") (name "Net-(F1-1-Pad1')") (class "Default")
      (node (ref "F1") (pin "1") (pinfunction "1_1") (pintype "passive"))
      (node (ref "F1") (pin "1'") (pinfunction "1_1'") (pintype "passive"))
      (node (ref "X1") (pin "2") (pinfunction "2_2") (pintype "passive"))
      (node (ref "X1") (pin "2'") (pinfunction "2_2'") (pintype "passive"))
    )
    (net (code "18") (name "Net-(F2-1-Pad1')") (class "Default")
      (node (ref "F2") (pin "1") (pinfunction "1_1") (pintype "passive"))
      (node (ref "F2") (pin "1'") (pinfunction "1_1'") (pintype "passive"))
      (node (ref "X2") (pin "2") (pinfunction "2_2") (pintype "passive"))
      (node (ref "X2") (pin "2'") (pinfunction "2_2'") (pintype "passive"))
    )
    (net (code "19") (name "Net-(F3-1-Pad1')") (class "Default")
      (node (ref "F3") (pin "1") (pinfunction "1_1") (pintype "passive"))
      (node (ref "F3") (pin "1'") (pinfunction "1_1'") (pintype "passive"))
      (node (ref "X3") (pin "2") (pinfunction "2_2") (pintype "passive"))
      (node (ref "X3") (pin "2'") (pinfunction "2_2'") (pintype "passive"))
    )
    (net (code "20") (name "Net-(F4-1-Pad1')") (class "Default")
      (node (ref "F4") (pin "1") (pinfunction "1_1") (pintype "passive"))
      (node (ref "F4") (pin "1'") (pinfunction "1_1'") (pintype "passive"))
      (node (ref "X4") (pin "2") (pinfunction "2_2") (pintype "passive"))
      (node (ref "X4") (pin "2'") (pinfunction "2_2'") (pintype "passive"))
    )
    (net (code "21") (name "Net-(F5-1-Pad1')") (class "Default")
      (node (ref "F5") (pin "1") (pinfunction "1_1") (pintype "passive"))
      (node (ref "F5") (pin "1'") (pinfunction "1_1'") (pintype "passive"))
      (node (ref "X5") (pin "2") (pinfunction "2_2") (pintype "passive"))
      (node (ref "X5") (pin "2'") (pinfunction "2_2'") (pintype "passive"))
    )
    (net (code "22") (name "Net-(F6-1-Pad1')") (class "Default")
      (node (ref "F6") (pin "1") (pinfunction "1_1") (pintype "passive"))
      (node (ref "F6") (pin "1'") (pinfunction "1_1'") (pintype "passive"))
      (node (ref "X6") (pin "2") (pinfunction "2_2") (pintype "passive"))
      (node (ref "X6") (pin "2'") (pinfunction "2_2'") (pintype "passive"))
    )
    (net (code "23") (name "Net-(F7-1-Pad1')") (class "Default")
      (node (ref "F7") (pin "1") (pinfunction "1_1") (pintype "passive"))
      (node (ref "F7") (pin "1'") (pinfunction "1_1'") (pintype "passive"))
      (node (ref "X7") (pin "2") (pinfunction "2_2") (pintype "passive"))
      (node (ref "X7") (pin "2'") (pinfunction "2_2'") (pintype "passive"))
    )
    (net (code "24") (name "Net-(F8-1-Pad1')") (class "Default")
      (node (ref "F8") (pin "1") (pinfunction "1_1") (pintype "passive"))
      (node (ref "F8") (pin "1'") (pinfunction "1_1'") (pintype "passive"))
      (node (ref "X8") (pin "2") (pinfunction "2_2") (pintype "passive"))
      (node (ref "X8") (pin "2'") (pinfunction "2_2'") (pintype "passive"))
    )
    (net (code "25") (name "Net-(F9-1-Pad1')") (class "Default")
      (node (ref "F9") (pin "1") (pinfunction "1_1") (pintype "passive"))
      (node (ref "F9") (pin "1'") (pinfunction "1_1'") (pintype "passive"))
      (node (ref "X9") (pin "2") (pinfunction "2_2") (pintype "passive"))
      (node (ref "X9") (pin "2'") (pinfunction "2_2'") (pintype "passive"))
    )
    (net (code "26") (name "Net-(F10-2-Pad2')") (class "Default")
      (node (ref "F10") (pin "2") (pinfunction "2_2") (pintype "passive"))
      (node (ref "F10") (pin "2'") (pinfunction "2_2'") (pintype "passive"))
      (node (ref "X10") (pin "1") (pinfunction "1_1") (pintype "passive"))
      (node (ref "X10") (pin "1'") (pinfunction "1_1'") (pintype "passive"))
    )
    (net (code "27") (name "Net-(F12-2-Pad2')") (class "Default")
      (node (ref "F12") (pin "2") (pinfunction "2_2") (pintype "passive"))
      (node (ref "F12") (pin "2'") (pinfunction "2_2'") (pintype "passive"))
      (node (ref "X12") (pin "1") (pinfunction "1_1") (pintype "passive"))
      (node (ref "X12") (pin "1'") (pinfunction "1_1'") (pintype "passive"))
      (node (ref "X12") (pin "2") (pinfunction "2_2") (pintype "passive"))
      (node (ref "X12") (pin "2'") (pinfunction "2_2'") (pintype "passive"))
    )
    (net (code "28") (name "Net-(F13-2-Pad2')") (class "Default")
      (node (ref "F13") (pin "2") (pinfunction "2_2") (pintype "passive"))
      (node (ref "F13") (pin "2'") (pinfunction "2_2'") (pintype "passive"))
      (node (ref "X13") (pin "1") (pinfunction "1_1") (pintype "passive"))
      (node (ref "X13") (pin "1'") (pinfunction "1_1'") (pintype "passive"))
    )
    (net (code "29") (name "Net-(K1A-1)") (class "Default")
      (node (ref "K1") (pin "A1") (pinfunction "1_A1") (pintype "passive"))
      (node (ref "V5") (pin "C") (pinfunction "C_C") (pintype "passive"))
    )
    (net (code "30") (name "Net-(K1A-2)") (class "Default")
      (node (ref "K1") (pin "A2") (pinfunction "2_A2") (pintype "passive"))
      (node (ref "Q1") (pin "3") (pinfunction "C_3") (pintype "passive"))
      (node (ref "V5") (pin "A") (pinfunction "A_A") (pintype "passive"))
    )
    (net (code "31") (name "Net-(K1B-O)") (class "Default")
      (node (ref "K1") (pin "12") (pinfunction "O_12") (pintype "passive"))
      (node (ref "X1") (pin "1") (pinfunction "1_1") (pintype "passive"))
      (node (ref "X1") (pin "1'") (pinfunction "1_1'") (pintype "passive"))
    )
    (net (code "32") (name "Net-(K1B-P)") (class "Default")
      (node (ref "F1") (pin "2") (pinfunction "2_2") (pintype "passive"))
      (node (ref "F1") (pin "2'") (pinfunction "2_2'") (pintype "passive"))
      (node (ref "K1") (pin "11") (pinfunction "P_11") (pintype "passive"))
    )
    (net (code "33") (name "Net-(K1B-S)") (class "Default")
      (node (ref "K1") (pin "14") (pinfunction "S_14") (pintype "passive"))
      (node (ref "X1") (pin "3") (pinfunction "3_3") (pintype "passive"))
      (node (ref "X1") (pin "3'") (pinfunction "3_3'") (pintype "passive"))
    )
    (net (code "34") (name "Net-(K2A-1)") (class "Default")
      (node (ref "K2") (pin "A1") (pinfunction "1_A1") (pintype "passive"))
      (node (ref "V6") (pin "C") (pinfunction "C_C") (pintype "passive"))
    )
    (net (code "35") (name "Net-(K2A-2)") (class "Default")
      (node (ref "K2") (pin "A2") (pinfunction "2_A2") (pintype "passive"))
      (node (ref "Q2") (pin "3") (pinfunction "C_3") (pintype "passive"))
      (node (ref "V6") (pin "A") (pinfunction "A_A") (pintype "passive"))
    )
    (net (code "36") (name "Net-(K2B-O)") (class "Default")
      (node (ref "K2") (pin "12") (pinfunction "O_12") (pintype "passive"))
      (node (ref "X2") (pin "1") (pinfunction "1_1") (pintype "passive"))
      (node (ref "X2") (pin "1'") (pinfunction "1_1'") (pintype "passive"))
    )
    (net (code "37") (name "Net-(K2B-P)") (class "Default")
      (node (ref "F2") (pin "2") (pinfunction "2_2") (pintype "passive"))
      (node (ref "F2") (pin "2'") (pinfunction "2_2'") (pintype "passive"))
      (node (ref "K2") (pin "11") (pinfunction "P_11") (pintype "passive"))
    )
    (net (code "38") (name "Net-(K2B-S)") (class "Default")
      (node (ref "K2") (pin "14") (pinfunction "S_14") (pintype "passive"))
      (node (ref "X2") (pin "3") (pinfunction "3_3") (pintype "passive"))
      (node (ref "X2") (pin "3'") (pinfunction "3_3'") (pintype "passive"))
    )
    (net (code "39") (name "Net-(K3A-1)") (class "Default")
      (node (ref "K3") (pin "A1") (pinfunction "1_A1") (pintype "passive"))
      (node (ref "V7") (pin "C") (pinfunction "C_C") (pintype "passive"))
    )
    (net (code "40") (name "Net-(K3A-2)") (class "Default")
      (node (ref "K3") (pin "A2") (pinfunction "2_A2") (pintype "passive"))
      (node (ref "Q3") (pin "3") (pinfunction "C_3") (pintype "passive"))
      (node (ref "V7") (pin "A") (pinfunction "A_A") (pintype "passive"))
    )
    (net (code "41") (name "Net-(K3B-O)") (class "Default")
      (node (ref "K3") (pin "12") (pinfunction "O_12") (pintype "passive"))
      (node (ref "X3") (pin "1") (pinfunction "1_1") (pintype "passive"))
      (node (ref "X3") (pin "1'") (pinfunction "1_1'") (pintype "passive"))
    )
    (net (code "42") (name "Net-(K3B-P)") (class "Default")
      (node (ref "F3") (pin "2") (pinfunction "2_2") (pintype "passive"))
      (node (ref "F3") (pin "2'") (pinfunction "2_2'") (pintype "passive"))
      (node (ref "K3") (pin "11") (pinfunction "P_11") (pintype "passive"))
    )
    (net (code "43") (name "Net-(K3B-S)") (class "Default")
      (node (ref "K3") (pin "14") (pinfunction "S_14") (pintype "passive"))
      (node (ref "X3") (pin "3") (pinfunction "3_3") (pintype "passive"))
      (node (ref "X3") (pin "3'") (pinfunction "3_3'") (pintype "passive"))
    )
    (net (code "44") (name "Net-(K4A-1)") (class "Default")
      (node (ref "K4") (pin "A1") (pinfunction "1_A1") (pintype "passive"))
      (node (ref "V8") (pin "C") (pinfunction "C_C") (pintype "passive"))
    )
    (net (code "45") (name "Net-(K4A-2)") (class "Default")
      (node (ref "K4") (pin "A2") (pinfunction "2_A2") (pintype "passive"))
      (node (ref "Q4") (pin "3") (pinfunction "C_3") (pintype "passive"))
      (node (ref "V8") (pin "A") (pinfunction "A_A") (pintype "passive"))
    )
    (net (code "46") (name "Net-(K4B-O)") (class "Default")
      (node (ref "K4") (pin "12") (pinfunction "O_12") (pintype "passive"))
      (node (ref "X4") (pin "1") (pinfunction "1_1") (pintype "passive"))
      (node (ref "X4") (pin "1'") (pinfunction "1_1'") (pintype "passive"))
    )
    (net (code "47") (name "Net-(K4B-P)") (class "Default")
      (node (ref "F4") (pin "2") (pinfunction "2_2") (pintype "passive"))
      (node (ref "F4") (pin "2'") (pinfunction "2_2'") (pintype "passive"))
      (node (ref "K4") (pin "11") (pinfunction "P_11") (pintype "passive"))
    )
    (net (code "48") (name "Net-(K4B-S)") (class "Default")
      (node (ref "K4") (pin "14") (pinfunction "S_14") (pintype "passive"))
      (node (ref "X4") (pin "3") (pinfunction "3_3") (pintype "passive"))
      (node (ref "X4") (pin "3'") (pinfunction "3_3'") (pintype "passive"))
    )
    (net (code "49") (name "Net-(K5A-1)") (class "Default")
      (node (ref "K5") (pin "A1") (pinfunction "1_A1") (pintype "passive"))
      (node (ref "V13") (pin "C") (pinfunction "C_C") (pintype "passive"))
    )
    (net (code "50") (name "Net-(K5A-2)") (class "Default")
      (node (ref "K5") (pin "A2") (pinfunction "2_A2") (pintype "passive"))
      (node (ref "Q5") (pin "3") (pinfunction "C_3") (pintype "passive"))
      (node (ref "V13") (pin "A") (pinfunction "A_A") (pintype "passive"))
    )
    (net (code "51") (name "Net-(K5B-O)") (class "Default")
      (node (ref "K5") (pin "12") (pinfunction "O_12") (pintype "passive"))
      (node (ref "X5") (pin "1") (pinfunction "1_1") (pintype "passive"))
      (node (ref "X5") (pin "1'") (pinfunction "1_1'") (pintype "passive"))
    )
    (net (code "52") (name "Net-(K5B-P)") (class "Default")
      (node (ref "F5") (pin "2") (pinfunction "2_2") (pintype "passive"))
      (node (ref "F5") (pin "2'") (pinfunction "2_2'") (pintype "passive"))
      (node (ref "K5") (pin "11") (pinfunction "P_11") (pintype "passive"))
    )
    (net (code "53") (name "Net-(K5B-S)") (class "Default")
      (node (ref "K5") (pin "14") (pinfunction "S_14") (pintype "passive"))
      (node (ref "X5") (pin "3") (pinfunction "3_3") (pintype "passive"))
      (node (ref "X5") (pin "3'") (pinfunction "3_3'") (pintype "passive"))
    )
    (net (code "54") (name "Net-(K6A-1)") (class "Default")
      (node (ref "K6") (pin "A1") (pinfunction "1_A1") (pintype "passive"))
      (node (ref "V14") (pin "C") (pinfunction "C_C") (pintype "passive"))
    )
    (net (code "55") (name "Net-(K6A-2)") (class "Default")
      (node (ref "K6") (pin "A2") (pinfunction "2_A2") (pintype "passive"))
      (node (ref "Q6") (pin "3") (pinfunction "C_3") (pintype "passive"))
      (node (ref "V14") (pin "A") (pinfunction "A_A") (pintype "passive"))
    )
    (net (code "56") (name "Net-(K6B-O)") (class "Default")
      (node (ref "K6") (pin "12") (pinfunction "O_12") (pintype "passive"))
      (node (ref "X6") (pin "1") (pinfunction "1_1") (pintype "passive"))
      (node (ref "X6") (pin "1'") (pinfunction "1_1'") (pintype "passive"))
    )
    (net (code "57") (name "Net-(K6B-P)") (class "Default")
      (node (ref "F6") (pin "2") (pinfunction "2_2") (pintype "passive"))
      (node (ref "F6") (pin "2'") (pinfunction "2_2'") (pintype "passive"))
      (node (ref "K6") (pin "11") (pinfunction "P_11") (pintype "passive"))
    )
    (net (code "58") (name "Net-(K6B-S)") (class "Default")
      (node (ref "K6") (pin "14") (pinfunction "S_14") (pintype "passive"))
      (node (ref "X6") (pin "3") (pinfunction "3_3") (pintype "passive"))
      (node (ref "X6") (pin "3'") (pinfunction "3_3'") (pintype "passive"))
    )
    (net (code "59") (name "Net-(K7A-1)") (class "Default")
      (node (ref "K7") (pin "A1") (pinfunction "1_A1") (pintype "passive"))
      (node (ref "V15") (pin "C") (pinfunction "C_C") (pintype "passive"))
    )
    (net (code "60") (name "Net-(K7A-2)") (class "Default")
      (node (ref "K7") (pin "A2") (pinfunction "2_A2") (pintype "passive"))
      (node (ref "Q7") (pin "3") (pinfunction "C_3") (pintype "passive"))
      (node (ref "V15") (pin "A") (pinfunction "A_A") (pintype "passive"))
    )
    (net (code "61") (name "Net-(K7B-O)") (class "Default")
      (node (ref "K7") (pin "12") (pinfunction "O_12") (pintype "passive"))
      (node (ref "X7") (pin "1") (pinfunction "1_1") (pintype "passive"))
      (node (ref "X7") (pin "1'") (pinfunction "1_1'") (pintype "passive"))
    )
    (net (code "62") (name "Net-(K7B-P)") (class "Default")
      (node (ref "F7") (pin "2") (pinfunction "2_2") (pintype "passive"))
      (node (ref "F7") (pin "2'") (pinfunction "2_2'") (pintype "passive"))
      (node (ref "K7") (pin "11") (pinfunction "P_11") (pintype "passive"))
    )
    (net (code "63") (name "Net-(K7B-S)") (class "Default")
      (node (ref "K7") (pin "14") (pinfunction "S_14") (pintype "passive"))
      (node (ref "X7") (pin "3") (pinfunction "3_3") (pintype "passive"))
      (node (ref "X7") (pin "3'") (pinfunction "3_3'") (pintype "passive"))
    )
    (net (code "64") (name "Net-(K8A-1)") (class "Default")
      (node (ref "K8") (pin "A1") (pinfunction "1_A1") (pintype "passive"))
      (node (ref "V16") (pin "C") (pinfunction "C_C") (pintype "passive"))
    )
    (net (code "65") (name "Net-(K8A-2)") (class "Default")
      (node (ref "K8") (pin "A2") (pinfunction "2_A2") (pintype "passive"))
      (node (ref "Q8") (pin "3") (pinfunction "C_3") (pintype "passive"))
      (node (ref "V16") (pin "A") (pinfunction "A_A") (pintype "passive"))
    )
    (net (code "66") (name "Net-(K8B-O)") (class "Default")
      (node (ref "K8") (pin "12") (pinfunction "O_12") (pintype "passive"))
      (node (ref "X8") (pin "1") (pinfunction "1_1") (pintype "passive"))
      (node (ref "X8") (pin "1'") (pinfunction "1_1'") (pintype "passive"))
    )
    (net (code "67") (name "Net-(K8B-P)") (class "Default")
      (node (ref "F8") (pin "2") (pinfunction "2_2") (pintype "passive"))
      (node (ref "F8") (pin "2'") (pinfunction "2_2'") (pintype "passive"))
      (node (ref "K8") (pin "11") (pinfunction "P_11") (pintype "passive"))
    )
    (net (code "68") (name "Net-(K8B-S)") (class "Default")
      (node (ref "K8") (pin "14") (pinfunction "S_14") (pintype "passive"))
      (node (ref "X8") (pin "3") (pinfunction "3_3") (pintype "passive"))
      (node (ref "X8") (pin "3'") (pinfunction "3_3'") (pintype "passive"))
    )
    (net (code "69") (name "Net-(K9A-1)") (class "Default")
      (node (ref "K9") (pin "A1") (pinfunction "1_A1") (pintype "passive"))
      (node (ref "V18") (pin "C") (pinfunction "C_C") (pintype "passive"))
    )
    (net (code "70") (name "Net-(K9A-2)") (class "Default")
      (node (ref "K9") (pin "A2") (pinfunction "2_A2") (pintype "passive"))
      (node (ref "Q9") (pin "3") (pinfunction "C_3") (pintype "passive"))
      (node (ref "V18") (pin "A") (pinfunction "A_A") (pintype "passive"))
    )
    (net (code "71") (name "Net-(K9B-O)") (class "Default")
      (node (ref "K9") (pin "12") (pinfunction "O_12") (pintype "passive"))
      (node (ref "X9") (pin "1") (pinfunction "1_1") (pintype "passive"))
      (node (ref "X9") (pin "1'") (pinfunction "1_1'") (pintype "passive"))
    )
    (net (code "72") (name "Net-(K9B-P)") (class "Default")
      (node (ref "F9") (pin "2") (pinfunction "2_2") (pintype "passive"))
      (node (ref "F9") (pin "2'") (pinfunction "2_2'") (pintype "passive"))
      (node (ref "K9") (pin "11") (pinfunction "P_11") (pintype "passive"))
    )
    (net (code "73") (name "Net-(K9B-S)") (class "Default")
      (node (ref "K9") (pin "14") (pinfunction "S_14") (pintype "passive"))
      (node (ref "X9") (pin "3") (pinfunction "3_3") (pintype "passive"))
      (node (ref "X9") (pin "3'") (pinfunction "3_3'") (pintype "passive"))
    )
    (net (code "74") (name "Net-(Q1-B)") (class "Default")
      (node (ref "Q1") (pin "1") (pinfunction "B_1") (pintype "passive"))
      (node (ref "R9") (pin "2") (pinfunction "2_2") (pintype "passive"))
    )
    (net (code "75") (name "Net-(Q2-B)") (class "Default")
      (node (ref "Q2") (pin "1") (pinfunction "B_1") (pintype "passive"))
      (node (ref "R10") (pin "2") (pinfunction "2_2") (pintype "passive"))
    )
    (net (code "76") (name "Net-(Q3-B)") (class "Default")
      (node (ref "Q3") (pin "1") (pinfunction "B_1") (pintype "passive"))
      (node (ref "R11") (pin "2") (pinfunction "2_2") (pintype "passive"))
    )
    (net (code "77") (name "Net-(Q4-B)") (class "Default")
      (node (ref "Q4") (pin "1") (pinfunction "B_1") (pintype "passive"))
      (node (ref "R12") (pin "2") (pinfunction "2_2") (pintype "passive"))
    )
    (net (code "78") (name "Net-(Q5-B)") (class "Default")
      (node (ref "Q5") (pin "1") (pinfunction "B_1") (pintype "passive"))
      (node (ref "R21") (pin "2") (pinfunction "2_2") (pintype "passive"))
    )
    (net (code "79") (name "Net-(Q6-B)") (class "Default")
      (node (ref "Q6") (pin "1") (pinfunction "B_1") (pintype "passive"))
      (node (ref "R22") (pin "2") (pinfunction "2_2") (pintype "passive"))
    )
    (net (code "80") (name "Net-(Q7-B)") (class "Default")
      (node (ref "Q7") (pin "1") (pinfunction "B_1") (pintype "passive"))
      (node (ref "R23") (pin "2") (pinfunction "2_2") (pintype "passive"))
    )
    (net (code "81") (name "Net-(Q8-B)") (class "Default")
      (node (ref "Q8") (pin "1") (pinfunction "B_1") (pintype "passive"))
      (node (ref "R24") (pin "2") (pinfunction "2_2") (pintype "passive"))
    )
    (net (code "82") (name "Net-(Q9-B)") (class "Default")
      (node (ref "Q9") (pin "1") (pinfunction "B_1") (pintype "passive"))
      (node (ref "R27") (pin "2") (pinfunction "2_2") (pintype "passive"))
    )
    (net (code "83") (name "Net-(S1-P)") (class "Default")
      (node (ref "R5") (pin "2") (pinfunction "2_2") (pintype "passive"))
      (node (ref "R9") (pin "1") (pinfunction "1_1") (pintype "passive"))
      (node (ref "S1") (pin "2") (pinfunction "P_2") (pintype "passive"))
      (node (ref "V1") (pin "3") (pinfunction "C_3") (pintype "passive"))
    )
    (net (code "84") (name "Net-(S2-P)") (class "Default")
      (node (ref "R10") (pin "1") (pinfunction "1_1") (pintype "passive"))
      (node (ref "R6") (pin "2") (pinfunction "2_2") (pintype "passive"))
      (node (ref "S2") (pin "2") (pinfunction "P_2") (pintype "passive"))
      (node (ref "V2") (pin "3") (pinfunction "C_3") (pintype "passive"))
    )
    (net (code "85") (name "Net-(S3-P)") (class "Default")
      (node (ref "R11") (pin "1") (pinfunction "1_1") (pintype "passive"))
      (node (ref "R7") (pin "2") (pinfunction "2_2") (pintype "passive"))
      (node (ref "S3") (pin "2") (pinfunction "P_2") (pintype "passive"))
      (node (ref "V3") (pin "3") (pinfunction "C_3") (pintype "passive"))
    )
    (net (code "86") (name "Net-(S4-P)") (class "Default")
      (node (ref "R12") (pin "1") (pinfunction "1_1") (pintype "passive"))
      (node (ref "R8") (pin "2") (pinfunction "2_2") (pintype "passive"))
      (node (ref "S4") (pin "2") (pinfunction "P_2") (pintype "passive"))
      (node (ref "V4") (pin "3") (pinfunction "C_3") (pintype "passive"))
    )
    (net (code "87") (name "Net-(S5-P)") (class "Default")
      (node (ref "R17") (pin "2") (pinfunction "2_2") (pintype "passive"))
      (node (ref "R21") (pin "1") (pinfunction "1_1") (pintype "passive"))
      (node (ref "S5") (pin "2") (pinfunction "P_2") (pintype "passive"))
      (node (ref "V9") (pin "3") (pinfunction "C_3") (pintype "passive"))
    )
    (net (code "88") (name "Net-(S6-P)") (class "Default")
      (node (ref "R18") (pin "2") (pinfunction "2_2") (pintype "passive"))
      (node (ref "R22") (pin "1") (pinfunction "1_1") (pintype "passive"))
      (node (ref "S6") (pin "2") (pinfunction "P_2") (pintype "passive"))
      (node (ref "V10") (pin "3") (pinfunction "C_3") (pintype "passive"))
    )
    (net (code "89") (name "Net-(S7-P)") (class "Default")
      (node (ref "R19") (pin "2") (pinfunction "2_2") (pintype "passive"))
      (node (ref "R23") (pin "1") (pinfunction "1_1") (pintype "passive"))
      (node (ref "S7") (pin "2") (pinfunction "P_2") (pintype "passive"))
      (node (ref "V11") (pin "3") (pinfunction "C_3") (pintype "passive"))
    )
    (net (code "90") (name "Net-(S8-P)") (class "Default")
      (node (ref "R20") (pin "2") (pinfunction "2_2") (pintype "passive"))
      (node (ref "R24") (pin "1") (pinfunction "1_1") (pintype "passive"))
      (node (ref "S8") (pin "2") (pinfunction "P_2") (pintype "passive"))
      (node (ref "V12") (pin "3") (pinfunction "C_3") (pintype "passive"))
    )
    (net (code "91") (name "Net-(S9-P)") (class "Default")
      (node (ref "R26") (pin "2") (pinfunction "2_2") (pintype "passive"))
      (node (ref "R27") (pin "1") (pinfunction "1_1") (pintype "passive"))
      (node (ref "S9") (pin "2") (pinfunction "P_2") (pintype "passive"))
      (node (ref "V17") (pin "3") (pinfunction "C_3") (pintype "passive"))
    )
    (net (code "92") (name "Net-(V1-A)") (class "Default")
      (node (ref "R1") (pin "1") (pinfunction "1_1") (pintype "passive"))
      (node (ref "V1") (pin "1") (pinfunction "A_1") (pintype "passive"))
    )
    (net (code "93") (name "Net-(V2-A)") (class "Default")
      (node (ref "R2") (pin "1") (pinfunction "1_1") (pintype "passive"))
      (node (ref "V2") (pin "1") (pinfunction "A_1") (pintype "passive"))
    )
    (net (code "94") (name "Net-(V3-A)") (class "Default")
      (node (ref "R3") (pin "1") (pinfunction "1_1") (pintype "passive"))
      (node (ref "V3") (pin "1") (pinfunction "A_1") (pintype "passive"))
    )
    (net (code "95") (name "Net-(V4-A)") (class "Default")
      (node (ref "R4") (pin "1") (pinfunction "1_1") (pintype "passive"))
      (node (ref "V4") (pin "1") (pinfunction "A_1") (pintype "passive"))
    )
    (net (code "96") (name "Net-(V9-A)") (class "Default")
      (node (ref "R13") (pin "1") (pinfunction "1_1") (pintype "passive"))
      (node (ref "V9") (pin "1") (pinfunction "A_1") (pintype "passive"))
    )
    (net (code "97") (name "Net-(V10-A)") (class "Default")
      (node (ref "R14") (pin "1") (pinfunction "1_1") (pintype "passive"))
      (node (ref "V10") (pin "1") (pinfunction "A_1") (pintype "passive"))
    )
    (net (code "98") (name "Net-(V11-A)") (class "Default")
      (node (ref "R15") (pin "1") (pinfunction "1_1") (pintype "passive"))
      (node (ref "V11") (pin "1") (pinfunction "A_1") (pintype "passive"))
    )
    (net (code "99") (name "Net-(V12-A)") (class "Default")
      (node (ref "R16") (pin "1") (pinfunction "1_1") (pintype "passive"))
      (node (ref "V12") (pin "1") (pinfunction "A_1") (pintype "passive"))
    )
    (net (code "100") (name "Net-(V17-A)") (class "Default")
      (node (ref "R25") (pin "1") (pinfunction "1_1") (pintype "passive"))
      (node (ref "V17") (pin "1") (pinfunction "A_1") (pintype "passive"))
    )
    (net (code "101") (name "P1") (class "Default")
      (node (ref "JP1") (pin "6") (pinfunction "6_6") (pintype "passive"))
      (node (ref "R1") (pin "2") (pinfunction "2_2") (pintype "passive"))
    )
    (net (code "102") (name "P2") (class "Default")
      (node (ref "JP1") (pin "4") (pinfunction "4_4") (pintype "passive"))
      (node (ref "R2") (pin "2") (pinfunction "2_2") (pintype "passive"))
    )
    (net (code "103") (name "P3") (class "Default")
      (node (ref "JP1") (pin "2") (pinfunction "2_2") (pintype "passive"))
      (node (ref "R3") (pin "2") (pinfunction "2_2") (pintype "passive"))
    )
    (net (code "104") (name "P4") (class "Default")
      (node (ref "JP1") (pin "1") (pinfunction "1_1") (pintype "passive"))
      (node (ref "R4") (pin "2") (pinfunction "2_2") (pintype "passive"))
    )
    (net (code "105") (name "P5") (class "Default")
      (node (ref "JP1") (pin "3") (pinfunction "3_3") (pintype "passive"))
      (node (ref "R13") (pin "2") (pinfunction "2_2") (pintype "passive"))
    )
    (net (code "106") (name "P6") (class "Default")
      (node (ref "JP1") (pin "5") (pinfunction "5_5") (pintype "passive"))
      (node (ref "R14") (pin "2") (pinfunction "2_2") (pintype "passive"))
    )
    (net (code "107") (name "P7") (class "Default")
      (node (ref "JP1") (pin "11") (pinfunction "11_11") (pintype "passive"))
      (node (ref "R15") (pin "2") (pinfunction "2_2") (pintype "passive"))
    )
    (net (code "108") (name "P8") (class "Default")
      (node (ref "JP1") (pin "13") (pinfunction "13_13") (pintype "passive"))
      (node (ref "R16") (pin "2") (pinfunction "2_2") (pintype "passive"))
    )
    (net (code "109") (name "P9") (class "Default")
      (node (ref "JP1") (pin "15") (pinfunction "15_15") (pintype "passive"))
      (node (ref "R25") (pin "2") (pinfunction "2_2") (pintype "passive"))
    )
    (net (code "110") (name "PE") (class "Default")
      (node (ref "X1") (pin "5") (pinfunction "5_5") (pintype "passive"))
      (node (ref "X1") (pin "5'") (pinfunction "5_5'") (pintype "passive"))
      (node (ref "X10") (pin "3") (pinfunction "3_3") (pintype "passive"))
      (node (ref "X10") (pin "3'") (pinfunction "3_3'") (pintype "passive"))
      (node (ref "X14") (pin "L3.1") (pinfunction "P3.1_L3.1") (pintype "bidirectional"))
      (node (ref "X14") (pin "L3.2") (pinfunction "P3.2_L3.2") (pintype "bidirectional"))
      (node (ref "X2") (pin "5") (pinfunction "5_5") (pintype "passive"))
      (node (ref "X2") (pin "5'") (pinfunction "5_5'") (pintype "passive"))
      (node (ref "X3") (pin "5") (pinfunction "5_5") (pintype "passive"))
      (node (ref "X3") (pin "5'") (pinfunction "5_5'") (pintype "passive"))
      (node (ref "X4") (pin "5") (pinfunction "5_5") (pintype "passive"))
      (node (ref "X4") (pin "5'") (pinfunction "5_5'") (pintype "passive"))
      (node (ref "X5") (pin "5") (pinfunction "5_5") (pintype "passive"))
      (node (ref "X5") (pin "5'") (pinfunction "5_5'") (pintype "passive"))
      (node (ref "X6") (pin "5") (pinfunction "5_5") (pintype "passive"))
      (node (ref "X6") (pin "5'") (pinfunction "5_5'") (pintype "passive"))
      (node (ref "X7") (pin "5") (pinfunction "5_5") (pintype "passive"))
      (node (ref "X7") (pin "5'") (pinfunction "5_5'") (pintype "passive"))
      (node (ref "X8") (pin "5") (pinfunction "5_5") (pintype "passive"))
      (node (ref "X8") (pin "5'") (pinfunction "5_5'") (pintype "passive"))
      (node (ref "X9") (pin "5") (pinfunction "5_5") (pintype "passive"))
      (node (ref "X9") (pin "5'") (pinfunction "5_5'") (pintype "passive"))
    )
    (net (code "111") (name "SCHIRM") (class "Default")
      (node (ref "X13") (pin "5") (pinfunction "5_5") (pintype "passive"))
      (node (ref "X13") (pin "5'") (pinfunction "5_5'") (pintype "passive"))
    )
    (net (code "112") (name "unconnected-(JP1-Pad14)") (class "Default")
      (node (ref "JP1") (pin "14") (pinfunction "14_14") (pintype "passive"))
    )
    (net (code "113") (name "unconnected-(JP1-Pad16)") (class "Default")
      (node (ref "JP1") (pin "16") (pinfunction "16_16") (pintype "passive"))
    )
    (net (code "114") (name "unconnected-(JP1-Pad17)") (class "Default")
      (node (ref "JP1") (pin "17") (pinfunction "17_17") (pintype "passive"))
    )
    (net (code "115") (name "unconnected-(JP1-Pad18)") (class "Default")
      (node (ref "JP1") (pin "18") (pinfunction "18_18") (pintype "passive"))
    )
  )
)
